# MPU_6050_Sheet1.net
KiCad netlist of a schematic drawn in Altium Designer
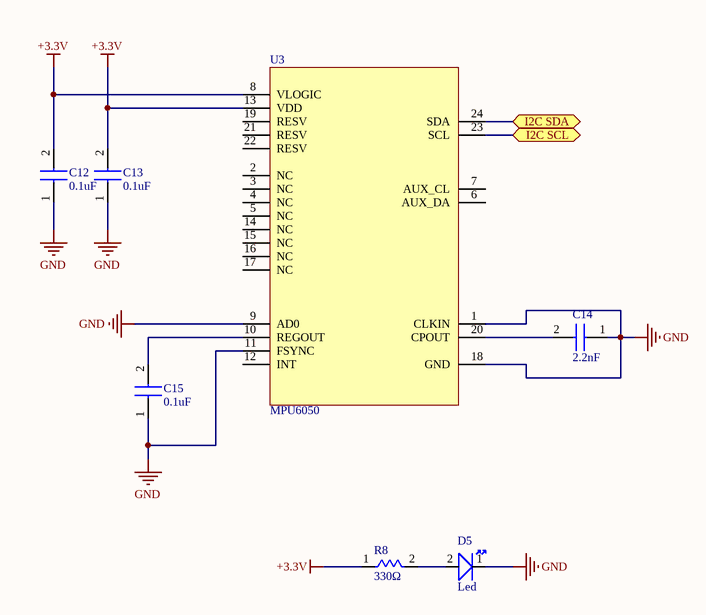
[diagram p0: MPU_6050_Sheet1.SchDoc]

(export (version "E")
  (design (tool "Eeschema 10.0.6"))
  (components
    (comp (ref "C12")
      (value "0.1uF")
      (footprint "CAP - 0603")
      (description "Capacitor")
      (libsource (lib "Faydali_Yuk_Schlib1") (part "CAP"))
    )
    (comp (ref "C13")
      (value "0.1uF")
      (footprint "CAP - 0603")
      (description "Capacitor")
      (libsource (lib "Faydali_Yuk_Schlib1") (part "CAP"))
    )
    (comp (ref "C14")
      (value "2.2nF")
      (footprint "CAP - 0603")
      (description "Capacitor")
      (libsource (lib "Faydali_Yuk_Schlib1") (part "CAP"))
    )
    (comp (ref "C15")
      (value "0.1uF")
      (footprint "CAP - 0603")
      (description "Capacitor")
      (libsource (lib "Faydali_Yuk_Schlib1") (part "CAP"))
    )
    (comp (ref "D5")
      (value "Led")
      (footprint "LED - 0603")
      (description "HL-PST-1608U51GC - LED SMD 0603 GREEN 500mcd 120° WATER CLEAR")
      (libsource (lib "Faydali_Yuk_Schlib1") (part "Led"))
    )
    (comp (ref "R8")
      (value "330Ω")
      (footprint "RES - 0603")
      (description "SMD Res")
      (libsource (lib "Faydali_Yuk_Schlib1") (part "Res"))
    )
    (comp (ref "U3")
      (value "MPU6050")
      (footprint "QFN50P400X400X90_HS-25N - duplicate")
      (description "MPU6050 GYRO")
      (libsource (lib "Faydali_Yuk_Schlib1") (part "MPU6050"))
    )
  )
  (nets
    (net (code "1") (name "+3.3V") (class "Default")
      (node (ref "C12") (pin "2") (pinfunction "2_2") (pintype "passive"))
      (node (ref "C13") (pin "2") (pinfunction "2_2") (pintype "passive"))
      (node (ref "R8") (pin "1") (pinfunction "1_1") (pintype "passive"))
      (node (ref "U3") (pin "13") (pinfunction "VDD_13") (pintype "passive"))
      (node (ref "U3") (pin "8") (pinfunction "VLOGIC_8") (pintype "passive"))
    )
    (net (code "2") (name "/I2C SCL") (class "Default")
      (node (ref "U3") (pin "23") (pinfunction "SCL_23") (pintype "passive"))
    )
    (net (code "3") (name "/I2C SDA") (class "Default")
      (node (ref "U3") (pin "24") (pinfunction "SDA_24") (pintype "passive"))
    )
    (net (code "4") (name "GND") (class "Default")
      (node (ref "C12") (pin "1") (pinfunction "1_1") (pintype "passive"))
      (node (ref "C13") (pin "1") (pinfunction "1_1") (pintype "passive"))
      (node (ref "C14") (pin "1") (pinfunction "1_1") (pintype "passive"))
      (node (ref "C15") (pin "1") (pinfunction "1_1") (pintype "passive"))
      (node (ref "D5") (pin "1") (pinfunction "1_1") (pintype "passive"))
      (node (ref "U3") (pin "1") (pinfunction "CLKIN_1") (pintype "passive"))
      (node (ref "U3") (pin "11") (pinfunction "FSYNC_11") (pintype "passive"))
      (node (ref "U3") (pin "18") (pinfunction "GND_18") (pintype "passive"))
      (node (ref "U3") (pin "9") (pinfunction "AD0_9") (pintype "passive"))
    )
    (net (code "5") (name "Net-(D5-Pad2)") (class "Default")
      (node (ref "D5") (pin "2") (pinfunction "2_2") (pintype "passive"))
      (node (ref "R8") (pin "2") (pinfunction "2_2") (pintype "passive"))
    )
    (net (code "6") (name "Net-(U3-CPOUT)") (class "Default")
      (node (ref "C14") (pin "2") (pinfunction "2_2") (pintype "passive"))
      (node (ref "U3") (pin "20") (pinfunction "CPOUT_20") (pintype "passive"))
    )
    (net (code "7") (name "Net-(U3-REGOUT)") (class "Default")
      (node (ref "C15") (pin "2") (pinfunction "2_2") (pintype "passive"))
      (node (ref "U3") (pin "10") (pinfunction "REGOUT_10") (pintype "passive"))
    )
    (net (code "8") (name "unconnected-(U3-AUX_CL-Pad7)") (class "Default")
      (node (ref "U3") (pin "7") (pinfunction "AUX_CL_7") (pintype "passive"))
    )
    (net (code "9") (name "unconnected-(U3-AUX_DA-Pad6)") (class "Default")
      (node (ref "U3") (pin "6") (pinfunction "AUX_DA_6") (pintype "passive"))
    )
    (net (code "10") (name "unconnected-(U3-INT-Pad12)") (class "Default")
      (node (ref "U3") (pin "12") (pinfunction "INT_12") (pintype "passive"))
    )
    (net (code "11") (name "unconnected-(U3-NC-Pad2)") (class "Default")
      (node (ref "U3") (pin "2") (pinfunction "NC_2") (pintype "passive"))
    )
    (net (code "12") (name "unconnected-(U3-NC-Pad3)") (class "Default")
      (node (ref "U3") (pin "3") (pinfunction "NC_3") (pintype "passive"))
    )
    (net (code "13") (name "unconnected-(U3-NC-Pad4)") (class "Default")
      (node (ref "U3") (pin "4") (pinfunction "NC_4") (pintype "passive"))
    )
    (net (code "14") (name "unconnected-(U3-NC-Pad5)") (class "Default")
      (node (ref "U3") (pin "5") (pinfunction "NC_5") (pintype "passive"))
    )
    (net (code "15") (name "unconnected-(U3-NC-Pad14)") (class "Default")
      (node (ref "U3") (pin "14") (pinfunction "NC_14") (pintype "passive"))
    )
    (net (code "16") (name "unconnected-(U3-NC-Pad15)") (class "Default")
      (node (ref "U3") (pin "15") (pinfunction "NC_15") (pintype "passive"))
    )
    (net (code "17") (name "unconnected-(U3-NC-Pad16)") (class "Default")
      (node (ref "U3") (pin "16") (pinfunction "NC_16") (pintype "passive"))
    )
    (net (code "18") (name "unconnected-(U3-NC-Pad17)") (class "Default")
      (node (ref "U3") (pin "17") (pinfunction "NC_17") (pintype "passive"))
    )
    (net (code "19") (name "unconnected-(U3-RESV-Pad19)") (class "Default")
      (node (ref "U3") (pin "19") (pinfunction "RESV_19") (pintype "passive"))
    )
    (net (code "20") (name "unconnected-(U3-RESV-Pad21)") (class "Default")
      (node (ref "U3") (pin "21") (pinfunction "RESV_21") (pintype "passive"))
    )
    (net (code "21") (name "unconnected-(U3-RESV-Pad22)") (class "Default")
      (node (ref "U3") (pin "22") (pinfunction "RESV_22") (pintype "passive"))
    )
  )
)
